# P08_Hi3531AV100_DDRC0_D.net
KiCad netlist of a schematic drawn in Altium Designer
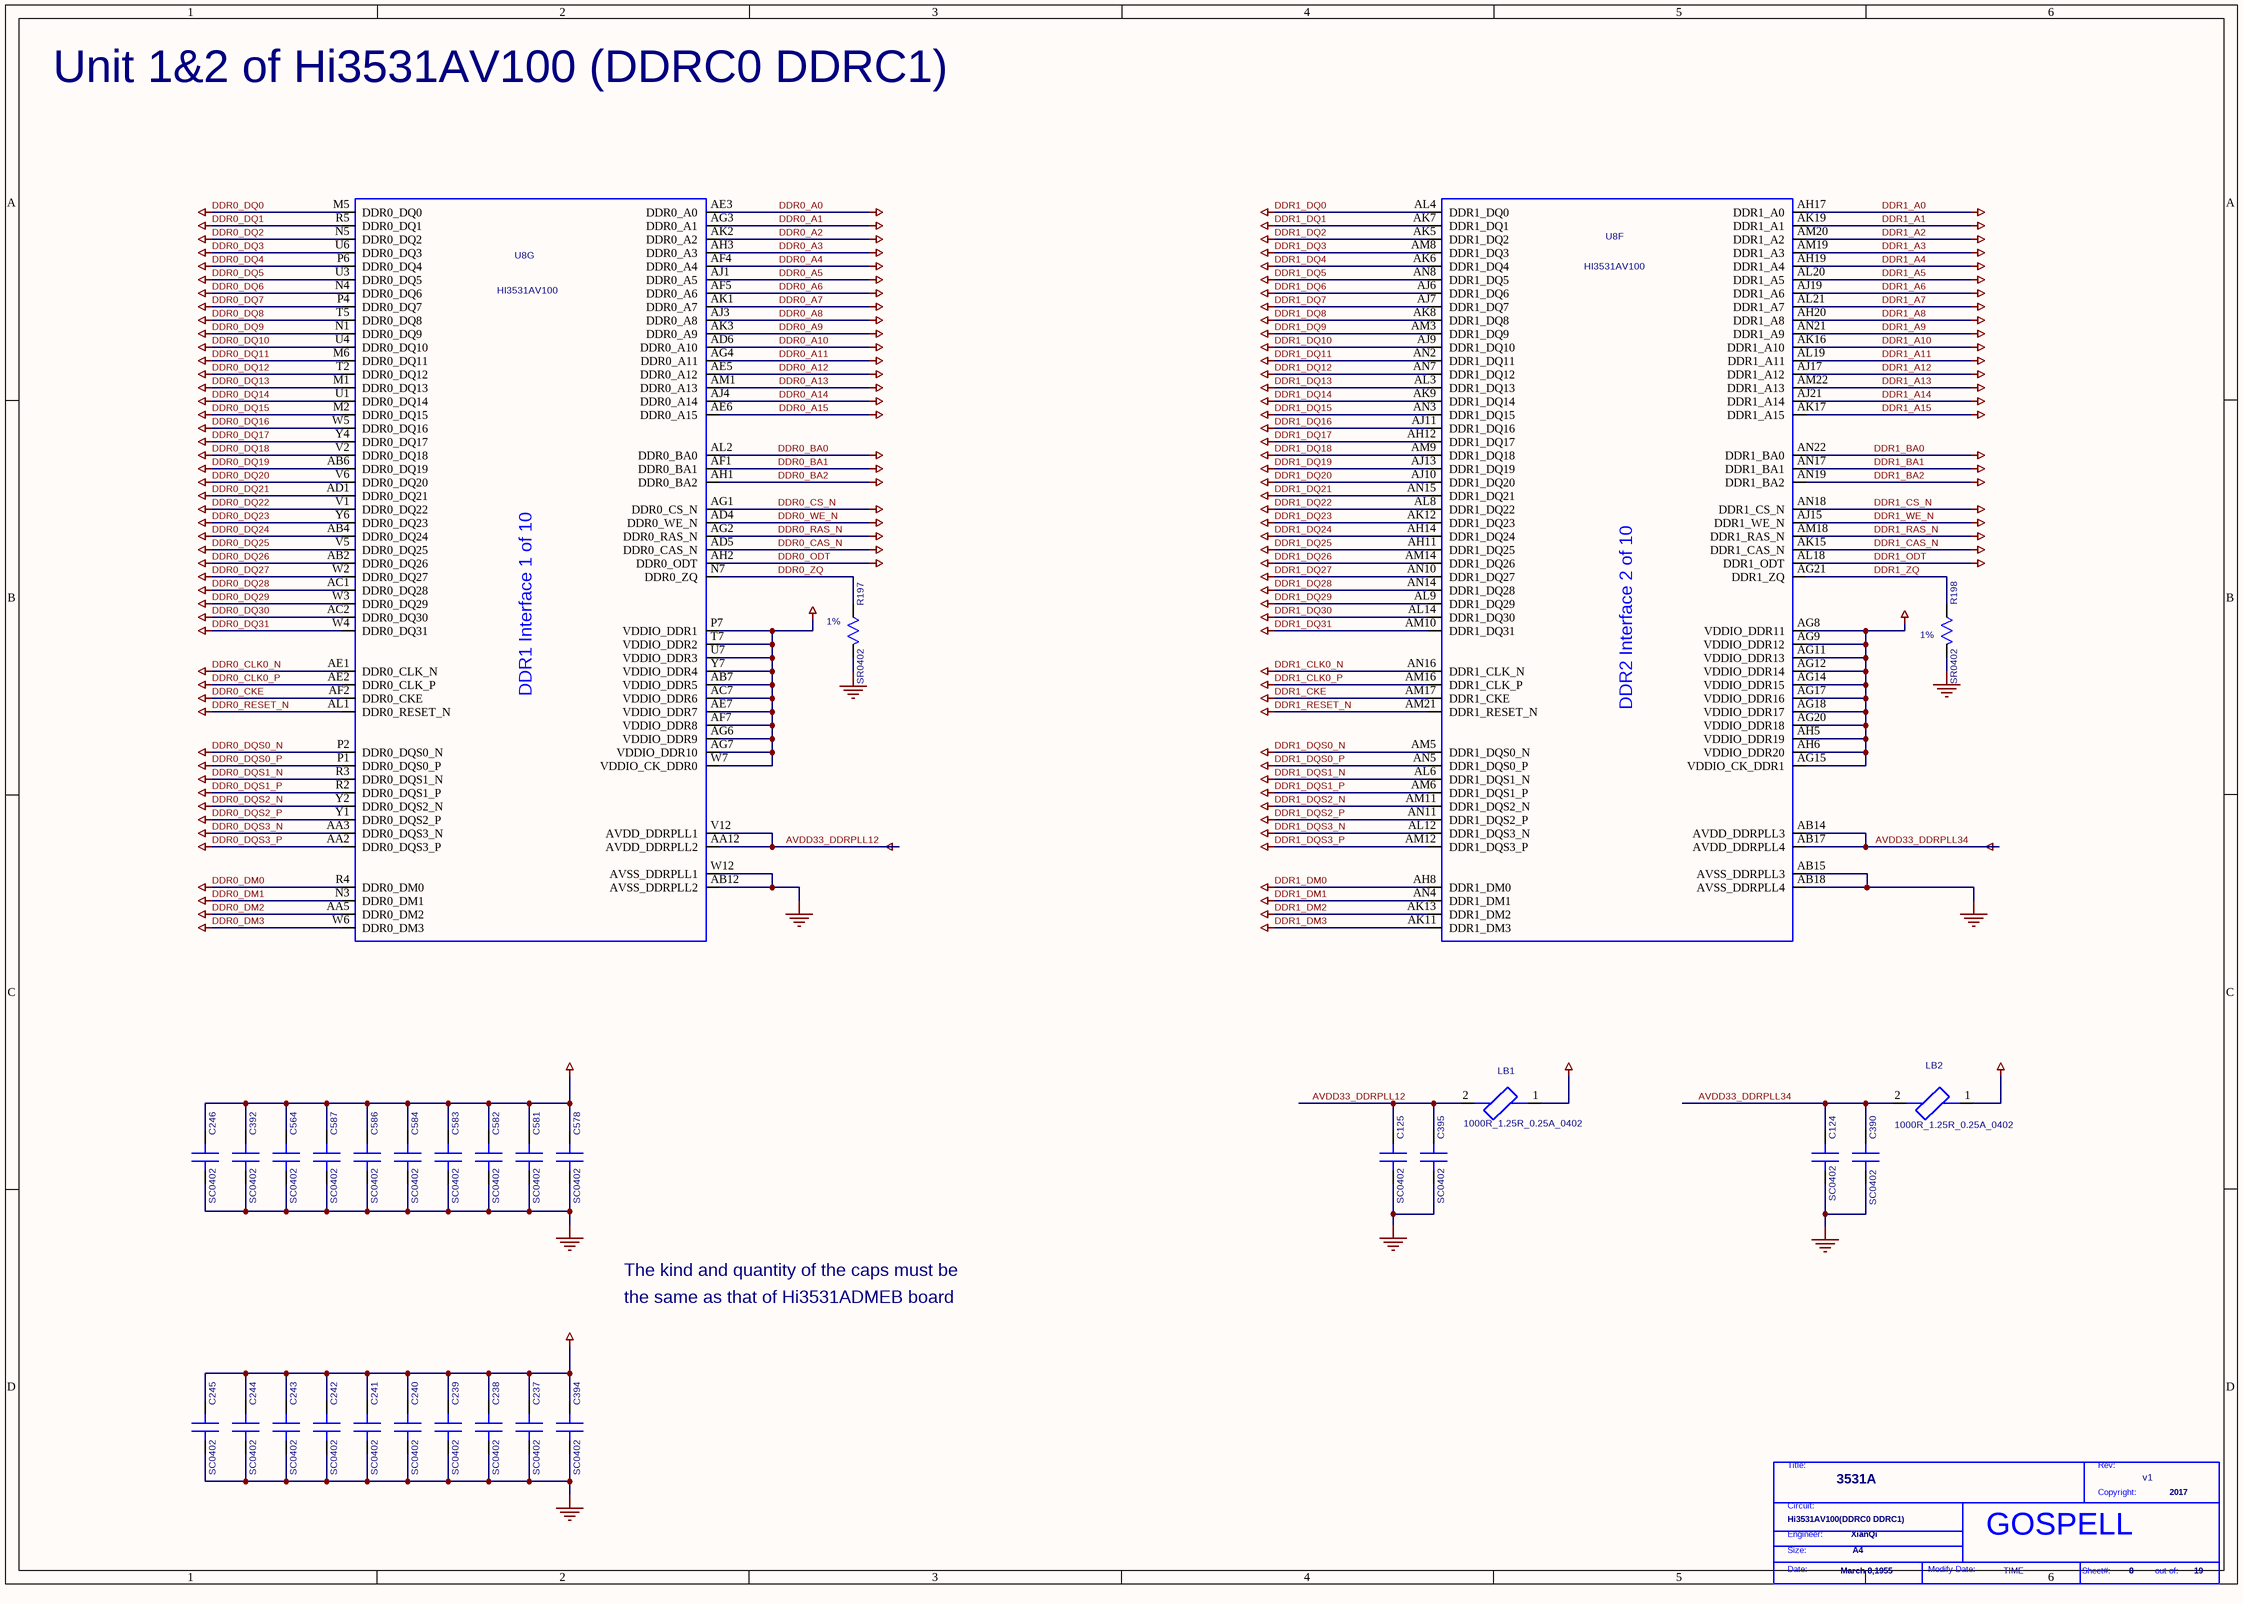
[diagram p0: P08 Hi3531AV100(DDRC0 D.SchDoc]

(export (version "E")
  (design (tool "Eeschema 10.0.6"))
  (components
    (comp (ref "C124") (value "SC0402") (libsource (lib "*") (part "C_0_Dup2")))
    (comp (ref "C125") (value "SC0402") (libsource (lib "*") (part "C_0_Dup2")))
    (comp (ref "C237") (value "SC0402") (libsource (lib "*") (part "C_0_Dup2")))
    (comp (ref "C238") (value "SC0402") (libsource (lib "*") (part "C_0_Dup2")))
    (comp (ref "C239") (value "SC0402") (libsource (lib "*") (part "C_0_Dup2")))
    (comp (ref "C240") (value "SC0402") (libsource (lib "*") (part "C_0_Dup2")))
    (comp (ref "C241") (value "SC0402") (libsource (lib "*") (part "C_0_Dup2")))
    (comp (ref "C242") (value "SC0402") (libsource (lib "*") (part "C_0_Dup2")))
    (comp (ref "C243") (value "SC0402") (libsource (lib "*") (part "C_0_Dup2")))
    (comp (ref "C244") (value "SC0402") (libsource (lib "*") (part "C_0_Dup2")))
    (comp (ref "C245") (value "SC0402") (libsource (lib "*") (part "C_0_Dup2")))
    (comp (ref "C246") (value "SC0402") (libsource (lib "*") (part "C_0_Dup2")))
    (comp (ref "C390") (value "SC0402") (libsource (lib "*") (part "C_0_Dup2")))
    (comp (ref "C392") (value "SC0402") (libsource (lib "*") (part "C_0_Dup2")))
    (comp (ref "C394") (value "SC0402") (libsource (lib "*") (part "C_0_Dup2")))
    (comp (ref "C395") (value "SC0402") (libsource (lib "*") (part "C_0_Dup2")))
    (comp (ref "C564") (value "SC0402") (libsource (lib "*") (part "C_0_Dup2")))
    (comp (ref "C578") (value "SC0402") (libsource (lib "*") (part "C_0_Dup2")))
    (comp (ref "C581") (value "SC0402") (libsource (lib "*") (part "C_0_Dup2")))
    (comp (ref "C582") (value "SC0402") (libsource (lib "*") (part "C_0_Dup2")))
    (comp (ref "C583") (value "SC0402") (libsource (lib "*") (part "C_0_Dup2")))
    (comp (ref "C584") (value "SC0402") (libsource (lib "*") (part "C_0_Dup2")))
    (comp (ref "C586") (value "SC0402") (libsource (lib "*") (part "C_0_Dup2")))
    (comp (ref "C587") (value "SC0402") (libsource (lib "*") (part "C_0_Dup2")))
    (comp (ref "LB1") (value "SL0402") (libsource (lib "*") (part "LB_0")))
    (comp (ref "LB2") (value "SL0402") (libsource (lib "*") (part "LB_0")))
    (comp (ref "R197") (value "SR0402") (libsource (lib "*") (part "R_1")))
    (comp (ref "R198") (value "SR0402") (libsource (lib "*") (part "R_1")))
    (comp (ref "U8")
      (value "BGA805-32-3333")
      (fields (field (name "DEVICE") "HI3531AV100"))
      (libsource (lib "*") (part "HI3531AV100_M2_17"))
    )
  )
  (nets
    (net (code "1") (name "/DDR0_ZQ") (class "Default")
      (node (ref "R197") (pin "1") (pinfunction "A_1") (pintype "passive"))
      (node (ref "U8") (pin "N7") (pinfunction "DDR0_ZQ_N7") (pintype "passive"))
    )
    (net (code "2") (name "/DDR1_ZQ") (class "Default")
      (node (ref "R198") (pin "1") (pinfunction "A_1") (pintype "passive"))
      (node (ref "U8") (pin "AG21") (pinfunction "DDR1_ZQ_AG21") (pintype "passive"))
    )
    (net (code "3") (name "1V5") (class "Default")
      (node (ref "C237") (pin "1") (pinfunction "A_1") (pintype "passive"))
      (node (ref "C238") (pin "1") (pinfunction "A_1") (pintype "passive"))
      (node (ref "C239") (pin "1") (pinfunction "A_1") (pintype "passive"))
      (node (ref "C240") (pin "1") (pinfunction "A_1") (pintype "passive"))
      (node (ref "C241") (pin "1") (pinfunction "A_1") (pintype "passive"))
      (node (ref "C242") (pin "1") (pinfunction "A_1") (pintype "passive"))
      (node (ref "C243") (pin "1") (pinfunction "A_1") (pintype "passive"))
      (node (ref "C244") (pin "1") (pinfunction "A_1") (pintype "passive"))
      (node (ref "C245") (pin "1") (pinfunction "A_1") (pintype "passive"))
      (node (ref "C246") (pin "1") (pinfunction "A_1") (pintype "passive"))
      (node (ref "C392") (pin "1") (pinfunction "A_1") (pintype "passive"))
      (node (ref "C394") (pin "1") (pinfunction "A_1") (pintype "passive"))
      (node (ref "C564") (pin "1") (pinfunction "A_1") (pintype "passive"))
      (node (ref "C578") (pin "1") (pinfunction "A_1") (pintype "passive"))
      (node (ref "C581") (pin "1") (pinfunction "A_1") (pintype "passive"))
      (node (ref "C582") (pin "1") (pinfunction "A_1") (pintype "passive"))
      (node (ref "C583") (pin "1") (pinfunction "A_1") (pintype "passive"))
      (node (ref "C584") (pin "1") (pinfunction "A_1") (pintype "passive"))
      (node (ref "C586") (pin "1") (pinfunction "A_1") (pintype "passive"))
      (node (ref "C587") (pin "1") (pinfunction "A_1") (pintype "passive"))
      (node (ref "U8") (pin "AB7") (pinfunction "VDDIO_DDR5_AB7") (pintype "passive"))
      (node (ref "U8") (pin "AC7") (pinfunction "VDDIO_DDR6_AC7") (pintype "passive"))
      (node (ref "U8") (pin "AE7") (pinfunction "VDDIO_DDR7_AE7") (pintype "passive"))
      (node (ref "U8") (pin "AF7") (pinfunction "VDDIO_DDR8_AF7") (pintype "passive"))
      (node (ref "U8") (pin "AG11") (pinfunction "VDDIO_DDR13_AG11") (pintype "passive"))
      (node (ref "U8") (pin "AG12") (pinfunction "VDDIO_DDR14_AG12") (pintype "passive"))
      (node (ref "U8") (pin "AG14") (pinfunction "VDDIO_DDR15_AG14") (pintype "passive"))
      (node (ref "U8") (pin "AG15") (pinfunction "VDDIO_CK_DDR1_AG15") (pintype "passive"))
      (node (ref "U8") (pin "AG17") (pinfunction "VDDIO_DDR16_AG17") (pintype "passive"))
      (node (ref "U8") (pin "AG18") (pinfunction "VDDIO_DDR17_AG18") (pintype "passive"))
      (node (ref "U8") (pin "AG20") (pinfunction "VDDIO_DDR18_AG20") (pintype "passive"))
      (node (ref "U8") (pin "AG6") (pinfunction "VDDIO_DDR9_AG6") (pintype "passive"))
      (node (ref "U8") (pin "AG7") (pinfunction "VDDIO_DDR10_AG7") (pintype "passive"))
      (node (ref "U8") (pin "AG8") (pinfunction "VDDIO_DDR11_AG8") (pintype "passive"))
      (node (ref "U8") (pin "AG9") (pinfunction "VDDIO_DDR12_AG9") (pintype "passive"))
      (node (ref "U8") (pin "AH5") (pinfunction "VDDIO_DDR19_AH5") (pintype "passive"))
      (node (ref "U8") (pin "AH6") (pinfunction "VDDIO_DDR20_AH6") (pintype "passive"))
      (node (ref "U8") (pin "P7") (pinfunction "VDDIO_DDR1_P7") (pintype "passive"))
      (node (ref "U8") (pin "T7") (pinfunction "VDDIO_DDR2_T7") (pintype "passive"))
      (node (ref "U8") (pin "U7") (pinfunction "VDDIO_DDR3_U7") (pintype "passive"))
      (node (ref "U8") (pin "W7") (pinfunction "VDDIO_CK_DDR0_W7") (pintype "passive"))
      (node (ref "U8") (pin "Y7") (pinfunction "VDDIO_DDR4_Y7") (pintype "passive"))
    )
    (net (code "4") (name "3V3") (class "Default")
      (node (ref "LB1") (pin "1") (pinfunction "1_1") (pintype "passive"))
      (node (ref "LB2") (pin "1") (pinfunction "1_1") (pintype "passive"))
    )
    (net (code "5") (name "AVDD33_DDRPLL12") (class "Default")
      (node (ref "C125") (pin "1") (pinfunction "A_1") (pintype "passive"))
      (node (ref "C395") (pin "1") (pinfunction "A_1") (pintype "passive"))
      (node (ref "LB1") (pin "2") (pinfunction "2_2") (pintype "passive"))
      (node (ref "U8") (pin "AA12") (pinfunction "AVDD_DDRPLL2_AA12") (pintype "passive"))
      (node (ref "U8") (pin "V12") (pinfunction "AVDD_DDRPLL1_V12") (pintype "passive"))
    )
    (net (code "6") (name "AVDD33_DDRPLL34") (class "Default")
      (node (ref "C124") (pin "1") (pinfunction "A_1") (pintype "passive"))
      (node (ref "C390") (pin "1") (pinfunction "A_1") (pintype "passive"))
      (node (ref "LB2") (pin "2") (pinfunction "2_2") (pintype "passive"))
      (node (ref "U8") (pin "AB14") (pinfunction "AVDD_DDRPLL3_AB14") (pintype "passive"))
      (node (ref "U8") (pin "AB17") (pinfunction "AVDD_DDRPLL4_AB17") (pintype "passive"))
    )
    (net (code "7") (name "DDR0_A0") (class "Default")
      (node (ref "U8") (pin "AE3") (pinfunction "DDR0_A0_AE3") (pintype "passive"))
    )
    (net (code "8") (name "DDR0_A1") (class "Default")
      (node (ref "U8") (pin "AG3") (pinfunction "DDR0_A1_AG3") (pintype "passive"))
    )
    (net (code "9") (name "DDR0_A2") (class "Default")
      (node (ref "U8") (pin "AK2") (pinfunction "DDR0_A2_AK2") (pintype "passive"))
    )
    (net (code "10") (name "DDR0_A3") (class "Default")
      (node (ref "U8") (pin "AH3") (pinfunction "DDR0_A3_AH3") (pintype "passive"))
    )
    (net (code "11") (name "DDR0_A4") (class "Default")
      (node (ref "U8") (pin "AF4") (pinfunction "DDR0_A4_AF4") (pintype "passive"))
    )
    (net (code "12") (name "DDR0_A5") (class "Default")
      (node (ref "U8") (pin "AJ1") (pinfunction "DDR0_A5_AJ1") (pintype "passive"))
    )
    (net (code "13") (name "DDR0_A6") (class "Default")
      (node (ref "U8") (pin "AF5") (pinfunction "DDR0_A6_AF5") (pintype "passive"))
    )
    (net (code "14") (name "DDR0_A7") (class "Default")
      (node (ref "U8") (pin "AK1") (pinfunction "DDR0_A7_AK1") (pintype "passive"))
    )
    (net (code "15") (name "DDR0_A8") (class "Default")
      (node (ref "U8") (pin "AJ3") (pinfunction "DDR0_A8_AJ3") (pintype "passive"))
    )
    (net (code "16") (name "DDR0_A9") (class "Default")
      (node (ref "U8") (pin "AK3") (pinfunction "DDR0_A9_AK3") (pintype "passive"))
    )
    (net (code "17") (name "DDR0_A10") (class "Default")
      (node (ref "U8") (pin "AD6") (pinfunction "DDR0_A10_AD6") (pintype "passive"))
    )
    (net (code "18") (name "DDR0_A11") (class "Default")
      (node (ref "U8") (pin "AG4") (pinfunction "DDR0_A11_AG4") (pintype "passive"))
    )
    (net (code "19") (name "DDR0_A12") (class "Default")
      (node (ref "U8") (pin "AE5") (pinfunction "DDR0_A12_AE5") (pintype "passive"))
    )
    (net (code "20") (name "DDR0_A13") (class "Default")
      (node (ref "U8") (pin "AM1") (pinfunction "DDR0_A13_AM1") (pintype "passive"))
    )
    (net (code "21") (name "DDR0_A14") (class "Default")
      (node (ref "U8") (pin "AJ4") (pinfunction "DDR0_A14_AJ4") (pintype "passive"))
    )
    (net (code "22") (name "DDR0_A15") (class "Default")
      (node (ref "U8") (pin "AE6") (pinfunction "DDR0_A15_AE6") (pintype "passive"))
    )
    (net (code "23") (name "DDR0_BA0") (class "Default")
      (node (ref "U8") (pin "AL2") (pinfunction "DDR0_BA0_AL2") (pintype "passive"))
    )
    (net (code "24") (name "DDR0_BA1") (class "Default")
      (node (ref "U8") (pin "AF1") (pinfunction "DDR0_BA1_AF1") (pintype "passive"))
    )
    (net (code "25") (name "DDR0_BA2") (class "Default")
      (node (ref "U8") (pin "AH1") (pinfunction "DDR0_BA2_AH1") (pintype "passive"))
    )
    (net (code "26") (name "DDR0_CAS_N") (class "Default")
      (node (ref "U8") (pin "AD5") (pinfunction "DDR0_CAS_N_AD5") (pintype "passive"))
    )
    (net (code "27") (name "DDR0_CKE") (class "Default")
      (node (ref "U8") (pin "AF2") (pinfunction "DDR0_CKE_AF2") (pintype "passive"))
    )
    (net (code "28") (name "DDR0_CLK0_N") (class "Default")
      (node (ref "U8") (pin "AE1") (pinfunction "DDR0_CLK_N_AE1") (pintype "passive"))
    )
    (net (code "29") (name "DDR0_CLK0_P") (class "Default")
      (node (ref "U8") (pin "AE2") (pinfunction "DDR0_CLK_P_AE2") (pintype "passive"))
    )
    (net (code "30") (name "DDR0_CS_N") (class "Default")
      (node (ref "U8") (pin "AG1") (pinfunction "DDR0_CS_N_AG1") (pintype "passive"))
    )
    (net (code "31") (name "DDR0_DM0") (class "Default")
      (node (ref "U8") (pin "R4") (pinfunction "DDR0_DM0_R4") (pintype "passive"))
    )
    (net (code "32") (name "DDR0_DM1") (class "Default")
      (node (ref "U8") (pin "N3") (pinfunction "DDR0_DM1_N3") (pintype "passive"))
    )
    (net (code "33") (name "DDR0_DM2") (class "Default")
      (node (ref "U8") (pin "AA5") (pinfunction "DDR0_DM2_AA5") (pintype "passive"))
    )
    (net (code "34") (name "DDR0_DM3") (class "Default")
      (node (ref "U8") (pin "W6") (pinfunction "DDR0_DM3_W6") (pintype "passive"))
    )
    (net (code "35") (name "DDR0_DQ0") (class "Default")
      (node (ref "U8") (pin "M5") (pinfunction "DDR0_DQ0_M5") (pintype "passive"))
    )
    (net (code "36") (name "DDR0_DQ1") (class "Default")
      (node (ref "U8") (pin "R5") (pinfunction "DDR0_DQ1_R5") (pintype "passive"))
    )
    (net (code "37") (name "DDR0_DQ2") (class "Default")
      (node (ref "U8") (pin "N5") (pinfunction "DDR0_DQ2_N5") (pintype "passive"))
    )
    (net (code "38") (name "DDR0_DQ3") (class "Default")
      (node (ref "U8") (pin "U6") (pinfunction "DDR0_DQ3_U6") (pintype "passive"))
    )
    (net (code "39") (name "DDR0_DQ4") (class "Default")
      (node (ref "U8") (pin "P6") (pinfunction "DDR0_DQ4_P6") (pintype "passive"))
    )
    (net (code "40") (name "DDR0_DQ5") (class "Default")
      (node (ref "U8") (pin "U3") (pinfunction "DDR0_DQ5_U3") (pintype "passive"))
    )
    (net (code "41") (name "DDR0_DQ6") (class "Default")
      (node (ref "U8") (pin "N4") (pinfunction "DDR0_DQ6_N4") (pintype "passive"))
    )
    (net (code "42") (name "DDR0_DQ7") (class "Default")
      (node (ref "U8") (pin "P4") (pinfunction "DDR0_DQ7_P4") (pintype "passive"))
    )
    (net (code "43") (name "DDR0_DQ8") (class "Default")
      (node (ref "U8") (pin "T5") (pinfunction "DDR0_DQ8_T5") (pintype "passive"))
    )
    (net (code "44") (name "DDR0_DQ9") (class "Default")
      (node (ref "U8") (pin "N1") (pinfunction "DDR0_DQ9_N1") (pintype "passive"))
    )
    (net (code "45") (name "DDR0_DQ10") (class "Default")
      (node (ref "U8") (pin "U4") (pinfunction "DDR0_DQ10_U4") (pintype "passive"))
    )
    (net (code "46") (name "DDR0_DQ11") (class "Default")
      (node (ref "U8") (pin "M6") (pinfunction "DDR0_DQ11_M6") (pintype "passive"))
    )
    (net (code "47") (name "DDR0_DQ12") (class "Default")
      (node (ref "U8") (pin "T2") (pinfunction "DDR0_DQ12_T2") (pintype "passive"))
    )
    (net (code "48") (name "DDR0_DQ13") (class "Default")
      (node (ref "U8") (pin "M1") (pinfunction "DDR0_DQ13_M1") (pintype "passive"))
    )
    (net (code "49") (name "DDR0_DQ14") (class "Default")
      (node (ref "U8") (pin "U1") (pinfunction "DDR0_DQ14_U1") (pintype "passive"))
    )
    (net (code "50") (name "DDR0_DQ15") (class "Default")
      (node (ref "U8") (pin "M2") (pinfunction "DDR0_DQ15_M2") (pintype "passive"))
    )
    (net (code "51") (name "DDR0_DQ16") (class "Default")
      (node (ref "U8") (pin "W5") (pinfunction "DDR0_DQ16_W5") (pintype "passive"))
    )
    (net (code "52") (name "DDR0_DQ17") (class "Default")
      (node (ref "U8") (pin "Y4") (pinfunction "DDR0_DQ17_Y4") (pintype "passive"))
    )
    (net (code "53") (name "DDR0_DQ18") (class "Default")
      (node (ref "U8") (pin "V2") (pinfunction "DDR0_DQ18_V2") (pintype "passive"))
    )
    (net (code "54") (name "DDR0_DQ19") (class "Default")
      (node (ref "U8") (pin "AB6") (pinfunction "DDR0_DQ19_AB6") (pintype "passive"))
    )
    (net (code "55") (name "DDR0_DQ20") (class "Default")
      (node (ref "U8") (pin "V6") (pinfunction "DDR0_DQ20_V6") (pintype "passive"))
    )
    (net (code "56") (name "DDR0_DQ21") (class "Default")
      (node (ref "U8") (pin "AD1") (pinfunction "DDR0_DQ21_AD1") (pintype "passive"))
    )
    (net (code "57") (name "DDR0_DQ22") (class "Default")
      (node (ref "U8") (pin "V1") (pinfunction "DDR0_DQ22_V1") (pintype "passive"))
    )
    (net (code "58") (name "DDR0_DQ23") (class "Default")
      (node (ref "U8") (pin "Y6") (pinfunction "DDR0_DQ23_Y6") (pintype "passive"))
    )
    (net (code "59") (name "DDR0_DQ24") (class "Default")
      (node (ref "U8") (pin "AB4") (pinfunction "DDR0_DQ24_AB4") (pintype "passive"))
    )
    (net (code "60") (name "DDR0_DQ25") (class "Default")
      (node (ref "U8") (pin "V5") (pinfunction "DDR0_DQ25_V5") (pintype "passive"))
    )
    (net (code "61") (name "DDR0_DQ26") (class "Default")
      (node (ref "U8") (pin "AB2") (pinfunction "DDR0_DQ26_AB2") (pintype "passive"))
    )
    (net (code "62") (name "DDR0_DQ27") (class "Default")
      (node (ref "U8") (pin "W2") (pinfunction "DDR0_DQ27_W2") (pintype "passive"))
    )
    (net (code "63") (name "DDR0_DQ28") (class "Default")
      (node (ref "U8") (pin "AC1") (pinfunction "DDR0_DQ28_AC1") (pintype "passive"))
    )
    (net (code "64") (name "DDR0_DQ29") (class "Default")
      (node (ref "U8") (pin "W3") (pinfunction "DDR0_DQ29_W3") (pintype "passive"))
    )
    (net (code "65") (name "DDR0_DQ30") (class "Default")
      (node (ref "U8") (pin "AC2") (pinfunction "DDR0_DQ30_AC2") (pintype "passive"))
    )
    (net (code "66") (name "DDR0_DQ31") (class "Default")
      (node (ref "U8") (pin "W4") (pinfunction "DDR0_DQ31_W4") (pintype "passive"))
    )
    (net (code "67") (name "DDR0_DQS0_N") (class "Default")
      (node (ref "U8") (pin "P2") (pinfunction "DDR0_DQS0_N_P2") (pintype "passive"))
    )
    (net (code "68") (name "DDR0_DQS0_P") (class "Default")
      (node (ref "U8") (pin "P1") (pinfunction "DDR0_DQS0_P_P1") (pintype "passive"))
    )
    (net (code "69") (name "DDR0_DQS1_N") (class "Default")
      (node (ref "U8") (pin "R3") (pinfunction "DDR0_DQS1_N_R3") (pintype "passive"))
    )
    (net (code "70") (name "DDR0_DQS1_P") (class "Default")
      (node (ref "U8") (pin "R2") (pinfunction "DDR0_DQS1_P_R2") (pintype "passive"))
    )
    (net (code "71") (name "DDR0_DQS2_N") (class "Default")
      (node (ref "U8") (pin "Y2") (pinfunction "DDR0_DQS2_N_Y2") (pintype "passive"))
    )
    (net (code "72") (name "DDR0_DQS2_P") (class "Default")
      (node (ref "U8") (pin "Y1") (pinfunction "DDR0_DQS2_P_Y1") (pintype "passive"))
    )
    (net (code "73") (name "DDR0_DQS3_N") (class "Default")
      (node (ref "U8") (pin "AA3") (pinfunction "DDR0_DQS3_N_AA3") (pintype "passive"))
    )
    (net (code "74") (name "DDR0_DQS3_P") (class "Default")
      (node (ref "U8") (pin "AA2") (pinfunction "DDR0_DQS3_P_AA2") (pintype "passive"))
    )
    (net (code "75") (name "DDR0_ODT") (class "Default")
      (node (ref "U8") (pin "AH2") (pinfunction "DDR0_ODT_AH2") (pintype "passive"))
    )
    (net (code "76") (name "DDR0_RAS_N") (class "Default")
      (node (ref "U8") (pin "AG2") (pinfunction "DDR0_RAS_N_AG2") (pintype "passive"))
    )
    (net (code "77") (name "DDR0_RESET_N") (class "Default")
      (node (ref "U8") (pin "AL1") (pinfunction "DDR0_RESET_N_AL1") (pintype "passive"))
    )
    (net (code "78") (name "DDR0_WE_N") (class "Default")
      (node (ref "U8") (pin "AD4") (pinfunction "DDR0_WE_N_AD4") (pintype "passive"))
    )
    (net (code "79") (name "DDR1_A0") (class "Default")
      (node (ref "U8") (pin "AH17") (pinfunction "DDR1_A0_AH17") (pintype "passive"))
    )
    (net (code "80") (name "DDR1_A1") (class "Default")
      (node (ref "U8") (pin "AK19") (pinfunction "DDR1_A1_AK19") (pintype "passive"))
    )
    (net (code "81") (name "DDR1_A2") (class "Default")
      (node (ref "U8") (pin "AM20") (pinfunction "DDR1_A2_AM20") (pintype "passive"))
    )
    (net (code "82") (name "DDR1_A3") (class "Default")
      (node (ref "U8") (pin "AM19") (pinfunction "DDR1_A3_AM19") (pintype "passive"))
    )
    (net (code "83") (name "DDR1_A4") (class "Default")
      (node (ref "U8") (pin "AH19") (pinfunction "DDR1_A4_AH19") (pintype "passive"))
    )
    (net (code "84") (name "DDR1_A5") (class "Default")
      (node (ref "U8") (pin "AL20") (pinfunction "DDR1_A5_AL20") (pintype "passive"))
    )
    (net (code "85") (name "DDR1_A6") (class "Default")
      (node (ref "U8") (pin "AJ19") (pinfunction "DDR1_A6_AJ19") (pintype "passive"))
    )
    (net (code "86") (name "DDR1_A7") (class "Default")
      (node (ref "U8") (pin "AL21") (pinfunction "DDR1_A7_AL21") (pintype "passive"))
    )
    (net (code "87") (name "DDR1_A8") (class "Default")
      (node (ref "U8") (pin "AH20") (pinfunction "DDR1_A8_AH20") (pintype "passive"))
    )
    (net (code "88") (name "DDR1_A9") (class "Default")
      (node (ref "U8") (pin "AN21") (pinfunction "DDR1_A9_AN21") (pintype "passive"))
    )
    (net (code "89") (name "DDR1_A10") (class "Default")
      (node (ref "U8") (pin "AK16") (pinfunction "DDR1_A10_AK16") (pintype "passive"))
    )
    (net (code "90") (name "DDR1_A11") (class "Default")
      (node (ref "U8") (pin "AL19") (pinfunction "DDR1_A11_AL19") (pintype "passive"))
    )
    (net (code "91") (name "DDR1_A12") (class "Default")
      (node (ref "U8") (pin "AJ17") (pinfunction "DDR1_A12_AJ17") (pintype "passive"))
    )
    (net (code "92") (name "DDR1_A13") (class "Default")
      (node (ref "U8") (pin "AM22") (pinfunction "DDR1_A13_AM22") (pintype "passive"))
    )
    (net (code "93") (name "DDR1_A14") (class "Default")
      (node (ref "U8") (pin "AJ21") (pinfunction "DDR1_A14_AJ21") (pintype "passive"))
    )
    (net (code "94") (name "DDR1_A15") (class "Default")
      (node (ref "U8") (pin "AK17") (pinfunction "DDR1_A15_AK17") (pintype "passive"))
    )
    (net (code "95") (name "DDR1_BA0") (class "Default")
      (node (ref "U8") (pin "AN22") (pinfunction "DDR1_BA0_AN22") (pintype "passive"))
    )
    (net (code "96") (name "DDR1_BA1") (class "Default")
      (node (ref "U8") (pin "AN17") (pinfunction "DDR1_BA1_AN17") (pintype "passive"))
    )
    (net (code "97") (name "DDR1_BA2") (class "Default")
      (node (ref "U8") (pin "AN19") (pinfunction "DDR1_BA2_AN19") (pintype "passive"))
    )
    (net (code "98") (name "DDR1_CAS_N") (class "Default")
      (node (ref "U8") (pin "AK15") (pinfunction "DDR1_CAS_N_AK15") (pintype "passive"))
    )
    (net (code "99") (name "DDR1_CKE") (class "Default")
      (node (ref "U8") (pin "AM17") (pinfunction "DDR1_CKE_AM17") (pintype "passive"))
    )
    (net (code "100") (name "DDR1_CLK0_N") (class "Default")
      (node (ref "U8") (pin "AN16") (pinfunction "DDR1_CLK_N_AN16") (pintype "passive"))
    )
    (net (code "101") (name "DDR1_CLK0_P") (class "Default")
      (node (ref "U8") (pin "AM16") (pinfunction "DDR1_CLK_P_AM16") (pintype "passive"))
    )
    (net (code "102") (name "DDR1_CS_N") (class "Default")
      (node (ref "U8") (pin "AN18") (pinfunction "DDR1_CS_N_AN18") (pintype "passive"))
    )
    (net (code "103") (name "DDR1_DM0") (class "Default")
      (node (ref "U8") (pin "AH8") (pinfunction "DDR1_DM0_AH8") (pintype "passive"))
    )
    (net (code "104") (name "DDR1_DM1") (class "Default")
      (node (ref "U8") (pin "AN4") (pinfunction "DDR1_DM1_AN4") (pintype "passive"))
    )
    (net (code "105") (name "DDR1_DM2") (class "Default")
      (node (ref "U8") (pin "AK13") (pinfunction "DDR1_DM2_AK13") (pintype "passive"))
    )
    (net (code "106") (name "DDR1_DM3") (class "Default")
      (node (ref "U8") (pin "AK11") (pinfunction "DDR1_DM3_AK11") (pintype "passive"))
    )
    (net (code "107") (name "DDR1_DQ0") (class "Default")
      (node (ref "U8") (pin "AL4") (pinfunction "DDR1_DQ0_AL4") (pintype "passive"))
    )
    (net (code "108") (name "DDR1_DQ1") (class "Default")
      (node (ref "U8") (pin "AK7") (pinfunction "DDR1_DQ1_AK7") (pintype "passive"))
    )
    (net (code "109") (name "DDR1_DQ2") (class "Default")
      (node (ref "U8") (pin "AK5") (pinfunction "DDR1_DQ2_AK5") (pintype "passive"))
    )
    (net (code "110") (name "DDR1_DQ3") (class "Default")
      (node (ref "U8") (pin "AM8") (pinfunction "DDR1_DQ3_AM8") (pintype "passive"))
    )
    (net (code "111") (name "DDR1_DQ4") (class "Default")
      (node (ref "U8") (pin "AK6") (pinfunction "DDR1_DQ4_AK6") (pintype "passive"))
    )
    (net (code "112") (name "DDR1_DQ5") (class "Default")
      (node (ref "U8") (pin "AN8") (pinfunction "DDR1_DQ5_AN8") (pintype "passive"))
    )
    (net (code "113") (name "DDR1_DQ6") (class "Default")
      (node (ref "U8") (pin "AJ6") (pinfunction "DDR1_DQ6_AJ6") (pintype "passive"))
    )
    (net (code "114") (name "DDR1_DQ7") (class "Default")
      (node (ref "U8") (pin "AJ7") (pinfunction "DDR1_DQ7_AJ7") (pintype "passive"))
    )
    (net (code "115") (name "DDR1_DQ8") (class "Default")
      (node (ref "U8") (pin "AK8") (pinfunction "DDR1_DQ8_AK8") (pintype "passive"))
    )
    (net (code "116") (name "DDR1_DQ9") (class "Default")
      (node (ref "U8") (pin "AM3") (pinfunction "DDR1_DQ9_AM3") (pintype "passive"))
    )
    (net (code "117") (name "DDR1_DQ10") (class "Default")
      (node (ref "U8") (pin "AJ9") (pinfunction "DDR1_DQ10_AJ9") (pintype "passive"))
    )
    (net (code "118") (name "DDR1_DQ11") (class "Default")
      (node (ref "U8") (pin "AN2") (pinfunction "DDR1_DQ11_AN2") (pintype "passive"))
    )
    (net (code "119") (name "DDR1_DQ12") (class "Default")
      (node (ref "U8") (pin "AN7") (pinfunction "DDR1_DQ12_AN7") (pintype "passive"))
    )
    (net (code "120") (name "DDR1_DQ13") (class "Default")
      (node (ref "U8") (pin "AL3") (pinfunction "DDR1_DQ13_AL3") (pintype "passive"))
    )
    (net (code "121") (name "DDR1_DQ14") (class "Default")
      (node (ref "U8") (pin "AK9") (pinfunction "DDR1_DQ14_AK9") (pintype "passive"))
    )
    (net (code "122") (name "DDR1_DQ15") (class "Default")
      (node (ref "U8") (pin "AN3") (pinfunction "DDR1_DQ15_AN3") (pintype "passive"))
    )
    (net (code "123") (name "DDR1_DQ16") (class "Default")
      (node (ref "U8") (pin "AJ11") (pinfunction "DDR1_DQ16_AJ11") (pintype "passive"))
    )
    (net (code "124") (name "DDR1_DQ17") (class "Default")
      (node (ref "U8") (pin "AH12") (pinfunction "DDR1_DQ17_AH12") (pintype "passive"))
    )
    (net (code "125") (name "DDR1_DQ18") (class "Default")
      (node (ref "U8") (pin "AM9") (pinfunction "DDR1_DQ18_AM9") (pintype "passive"))
    )
    (net (code "126") (name "DDR1_DQ19") (class "Default")
      (node (ref "U8") (pin "AJ13") (pinfunction "DDR1_DQ19_AJ13") (pintype "passive"))
    )
    (net (code "127") (name "DDR1_DQ20") (class "Default")
      (node (ref "U8") (pin "AJ10") (pinfunction "DDR1_DQ20_AJ10") (pintype "passive"))
    )
    (net (code "128") (name "DDR1_DQ21") (class "Default")
      (node (ref "U8") (pin "AN15") (pinfunction "DDR1_DQ21_AN15") (pintype "passive"))
    )
    (net (code "129") (name "DDR1_DQ22") (class "Default")
      (node (ref "U8") (pin "AL8") (pinfunction "DDR1_DQ22_AL8") (pintype "passive"))
    )
    (net (code "130") (name "DDR1_DQ23") (class "Default")
      (node (ref "U8") (pin "AK12") (pinfunction "DDR1_DQ23_AK12") (pintype "passive"))
    )
    (net (code "131") (name "DDR1_DQ24") (class "Default")
      (node (ref "U8") (pin "AH14") (pinfunction "DDR1_DQ24_AH14") (pintype "passive"))
    )
    (net (code "132") (name "DDR1_DQ25") (class "Default")
      (node (ref "U8") (pin "AH11") (pinfunction "DDR1_DQ25_AH11") (pintype "passive"))
    )
    (net (code "133") (name "DDR1_DQ26") (class "Default")
      (node (ref "U8") (pin "AM14") (pinfunction "DDR1_DQ26_AM14") (pintype "passive"))
    )
    (net (code "134") (name "DDR1_DQ27") (class "Default")
      (node (ref "U8") (pin "AN10") (pinfunction "DDR1_DQ27_AN10") (pintype "passive"))
    )
    (net (code "135") (name "DDR1_DQ28") (class "Default")
      (node (ref "U8") (pin "AN14") (pinfunction "DDR1_DQ28_AN14") (pintype "passive"))
    )
    (net (code "136") (name "DDR1_DQ29") (class "Default")
      (node (ref "U8") (pin "AL9") (pinfunction "DDR1_DQ29_AL9") (pintype "passive"))
    )
    (net (code "137") (name "DDR1_DQ30") (class "Default")
      (node (ref "U8") (pin "AL14") (pinfunction "DDR1_DQ30_AL14") (pintype "passive"))
    )
    (net (code "138") (name "DDR1_DQ31") (class "Default")
      (node (ref "U8") (pin "AM10") (pinfunction "DDR1_DQ31_AM10") (pintype "passive"))
    )
    (net (code "139") (name "DDR1_DQS0_N") (class "Default")
      (node (ref "U8") (pin "AM5") (pinfunction "DDR1_DQS0_N_AM5") (pintype "passive"))
    )
    (net (code "140") (name "DDR1_DQS0_P") (class "Default")
      (node (ref "U8") (pin "AN5") (pinfunction "DDR1_DQS0_P_AN5") (pintype "passive"))
    )
    (net (code "141") (name "DDR1_DQS1_N") (class "Default")
      (node (ref "U8") (pin "AL6") (pinfunction "DDR1_DQS1_N_AL6") (pintype "passive"))
    )
    (net (code "142") (name "DDR1_DQS1_P") (class "Default")
      (node (ref "U8") (pin "AM6") (pinfunction "DDR1_DQS1_P_AM6") (pintype "passive"))
    )
    (net (code "143") (name "DDR1_DQS2_N") (class "Default")
      (node (ref "U8") (pin "AM11") (pinfunction "DDR1_DQS2_N_AM11") (pintype "passive"))
    )
    (net (code "144") (name "DDR1_DQS2_P") (class "Default")
      (node (ref "U8") (pin "AN11") (pinfunction "DDR1_DQS2_P_AN11") (pintype "passive"))
    )
    (net (code "145") (name "DDR1_DQS3_N") (class "Default")
      (node (ref "U8") (pin "AL12") (pinfunction "DDR1_DQS3_N_AL12") (pintype "passive"))
    )
    (net (code "146") (name "DDR1_DQS3_P") (class "Default")
      (node (ref "U8") (pin "AM12") (pinfunction "DDR1_DQS3_P_AM12") (pintype "passive"))
    )
    (net (code "147") (name "DDR1_ODT") (class "Default")
      (node (ref "U8") (pin "AL18") (pinfunction "DDR1_ODT_AL18") (pintype "passive"))
    )
    (net (code "148") (name "DDR1_RAS_N") (class "Default")
      (node (ref "U8") (pin "AM18") (pinfunction "DDR1_RAS_N_AM18") (pintype "passive"))
    )
    (net (code "149") (name "DDR1_RESET_N") (class "Default")
      (node (ref "U8") (pin "AM21") (pinfunction "DDR1_RESET_N_AM21") (pintype "passive"))
    )
    (net (code "150") (name "DDR1_WE_N") (class "Default")
      (node (ref "U8") (pin "AJ15") (pinfunction "DDR1_WE_N_AJ15") (pintype "passive"))
    )
    (net (code "151") (name "GND") (class "Default")
      (node (ref "C124") (pin "2") (pinfunction "B_2") (pintype "passive"))
      (node (ref "C125") (pin "2") (pinfunction "B_2") (pintype "passive"))
      (node (ref "C237") (pin "2") (pinfunction "B_2") (pintype "passive"))
      (node (ref "C238") (pin "2") (pinfunction "B_2") (pintype "passive"))
      (node (ref "C239") (pin "2") (pinfunction "B_2") (pintype "passive"))
      (node (ref "C240") (pin "2") (pinfunction "B_2") (pintype "passive"))
      (node (ref "C241") (pin "2") (pinfunction "B_2") (pintype "passive"))
      (node (ref "C242") (pin "2") (pinfunction "B_2") (pintype "passive"))
      (node (ref "C243") (pin "2") (pinfunction "B_2") (pintype "passive"))
      (node (ref "C244") (pin "2") (pinfunction "B_2") (pintype "passive"))
      (node (ref "C245") (pin "2") (pinfunction "B_2") (pintype "passive"))
      (node (ref "C246") (pin "2") (pinfunction "B_2") (pintype "passive"))
      (node (ref "C390") (pin "2") (pinfunction "B_2") (pintype "passive"))
      (node (ref "C392") (pin "2") (pinfunction "B_2") (pintype "passive"))
      (node (ref "C394") (pin "2") (pinfunction "B_2") (pintype "passive"))
      (node (ref "C395") (pin "2") (pinfunction "B_2") (pintype "passive"))
      (node (ref "C564") (pin "2") (pinfunction "B_2") (pintype "passive"))
      (node (ref "C578") (pin "2") (pinfunction "B_2") (pintype "passive"))
      (node (ref "C581") (pin "2") (pinfunction "B_2") (pintype "passive"))
      (node (ref "C582") (pin "2") (pinfunction "B_2") (pintype "passive"))
      (node (ref "C583") (pin "2") (pinfunction "B_2") (pintype "passive"))
      (node (ref "C584") (pin "2") (pinfunction "B_2") (pintype "passive"))
      (node (ref "C586") (pin "2") (pinfunction "B_2") (pintype "passive"))
      (node (ref "C587") (pin "2") (pinfunction "B_2") (pintype "passive"))
      (node (ref "R197") (pin "2") (pinfunction "B_2") (pintype "passive"))
      (node (ref "R198") (pin "2") (pinfunction "B_2") (pintype "passive"))
      (node (ref "U8") (pin "AB12") (pinfunction "AVSS_DDRPLL2_AB12") (pintype "passive"))
      (node (ref "U8") (pin "AB15") (pinfunction "AVSS_DDRPLL3_AB15") (pintype "passive"))
      (node (ref "U8") (pin "AB18") (pinfunction "AVSS_DDRPLL4_AB18") (pintype "passive"))
      (node (ref "U8") (pin "W12") (pinfunction "AVSS_DDRPLL1_W12") (pintype "passive"))
    )
  )
)
